# echo-dot-4th-gen.net
KiCad netlist of a schematic drawn in EasyEDA
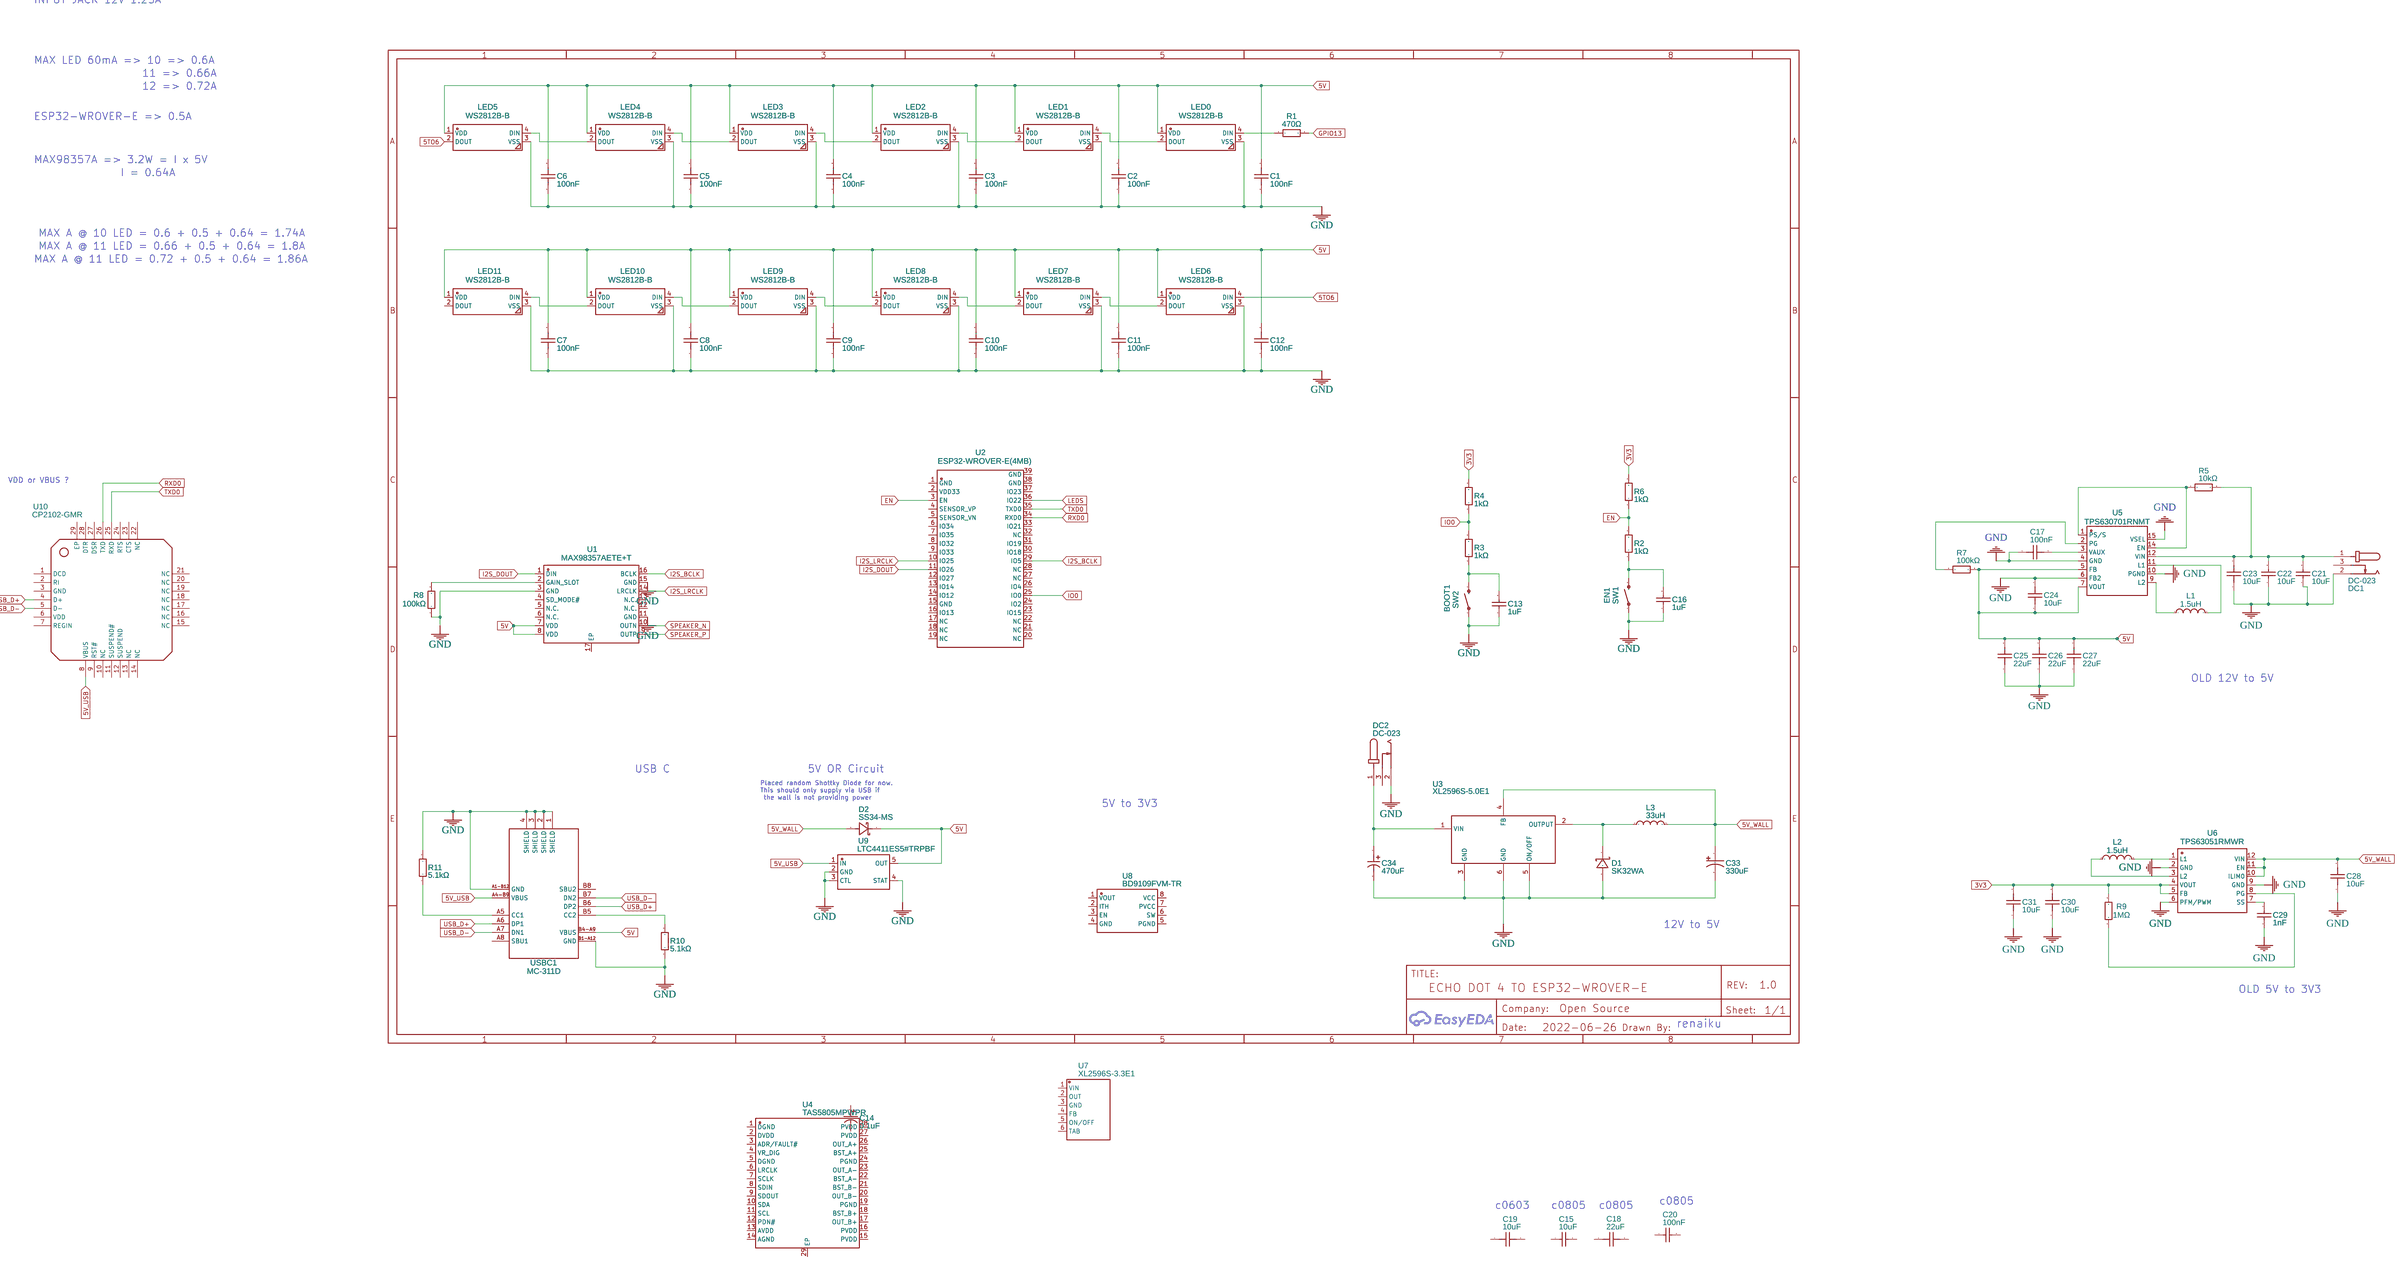
[diagram p0: schematic sheet]

(export (version "E")
  (design (tool "Eeschema 10.0.6"))
  (components
    (comp (ref "BOOT1")
      (value "SW2")
      (fields (field (name "BOM_Manufacturer Part") "?"))
      (libsource (lib "") (part "Unknown_1250_-170"))
    )
    (comp (ref "C1")
      (value "100nF")
      (fields
        (field (name "BOM_Manufacturer Part") "CC0603JRX7R7BB104")
        (field (name "BOM_Supplier Part") "C109474")
      )
      (libsource (lib "") (part "CC0603JRX7R7BB104"))
    )
    (comp (ref "C2")
      (value "100nF")
      (fields
        (field (name "BOM_Manufacturer Part") "CC0603JRX7R7BB104")
        (field (name "BOM_Supplier Part") "C109474")
      )
      (libsource (lib "") (part "CC0603JRX7R7BB104"))
    )
    (comp (ref "C3")
      (value "100nF")
      (fields
        (field (name "BOM_Manufacturer Part") "CC0603JRX7R7BB104")
        (field (name "BOM_Supplier Part") "C109474")
      )
      (libsource (lib "") (part "CC0603JRX7R7BB104"))
    )
    (comp (ref "C4")
      (value "100nF")
      (fields
        (field (name "BOM_Manufacturer Part") "CC0603JRX7R7BB104")
        (field (name "BOM_Supplier Part") "C109474")
      )
      (libsource (lib "") (part "CC0603JRX7R7BB104"))
    )
    (comp (ref "C5")
      (value "100nF")
      (fields
        (field (name "BOM_Manufacturer Part") "CC0603JRX7R7BB104")
        (field (name "BOM_Supplier Part") "C109474")
      )
      (libsource (lib "") (part "CC0603JRX7R7BB104"))
    )
    (comp (ref "C6")
      (value "100nF")
      (fields
        (field (name "BOM_Manufacturer Part") "CC0603JRX7R7BB104")
        (field (name "BOM_Supplier Part") "C109474")
      )
      (libsource (lib "") (part "CC0603JRX7R7BB104"))
    )
    (comp (ref "C7")
      (value "100nF")
      (fields
        (field (name "BOM_Manufacturer Part") "CC0603JRX7R7BB104")
        (field (name "BOM_Supplier Part") "C109474")
      )
      (libsource (lib "") (part "CC0603JRX7R7BB104"))
    )
    (comp (ref "C8")
      (value "100nF")
      (fields
        (field (name "BOM_Manufacturer Part") "CC0603JRX7R7BB104")
        (field (name "BOM_Supplier Part") "C109474")
      )
      (libsource (lib "") (part "CC0603JRX7R7BB104"))
    )
    (comp (ref "C9")
      (value "100nF")
      (fields
        (field (name "BOM_Manufacturer Part") "CC0603JRX7R7BB104")
        (field (name "BOM_Supplier Part") "C109474")
      )
      (libsource (lib "") (part "CC0603JRX7R7BB104"))
    )
    (comp (ref "C10")
      (value "100nF")
      (fields
        (field (name "BOM_Manufacturer Part") "CC0603JRX7R7BB104")
        (field (name "BOM_Supplier Part") "C109474")
      )
      (libsource (lib "") (part "CC0603JRX7R7BB104"))
    )
    (comp (ref "C11")
      (value "100nF")
      (fields
        (field (name "BOM_Manufacturer Part") "CC0603JRX7R7BB104")
        (field (name "BOM_Supplier Part") "C109474")
      )
      (libsource (lib "") (part "CC0603JRX7R7BB104"))
    )
    (comp (ref "C12")
      (value "100nF")
      (fields
        (field (name "BOM_Manufacturer Part") "CC0603JRX7R7BB104")
        (field (name "BOM_Supplier Part") "C109474")
      )
      (libsource (lib "") (part "CC0603JRX7R7BB104"))
    )
    (comp (ref "C13")
      (value "1uF")
      (fields
        (field (name "BOM_Manufacturer Part") "CC0603KRX5R6BB105")
        (field (name "BOM_Supplier Part") "C106214")
      )
      (libsource (lib "") (part "CC0603KRX5R6BB105"))
    )
    (comp (ref "C14")
      (value "0.1uF")
      (fields
        (field (name "BOM_Manufacturer Part") "0.1uF 50V 4*7")
        (field (name "BOM_Supplier Part") "C45664")
      )
      (libsource (lib "") (part "0.1uF 50V 4*7"))
    )
    (comp (ref "C15")
      (value "10uF")
      (fields
        (field (name "BOM_Manufacturer Part") "CL21A106KAYNNNE")
        (field (name "BOM_Supplier Part") "C15850")
      )
      (libsource (lib "") (part "CL21A106KAYNNNE_1"))
    )
    (comp (ref "C16")
      (value "1uF")
      (fields
        (field (name "BOM_Manufacturer Part") "CC0603KRX5R6BB105")
        (field (name "BOM_Supplier Part") "C106214")
      )
      (libsource (lib "") (part "CC0603KRX5R6BB105"))
    )
    (comp (ref "C17")
      (value "100nF")
      (fields
        (field (name "BOM_Manufacturer Part") "CC0603KRX7R9BB104")
        (field (name "BOM_Supplier Part") "C14663")
      )
      (libsource (lib "") (part "CC0603KRX7R9BB104"))
    )
    (comp (ref "C18")
      (value "22uF")
      (fields
        (field (name "BOM_Manufacturer Part") "CL21A226MAQNNNE")
        (field (name "BOM_Supplier Part") "C45783")
      )
      (libsource (lib "") (part "CL21A226MAQNNNE"))
    )
    (comp (ref "C19")
      (value "10uF")
      (fields
        (field (name "BOM_Manufacturer Part") "CL10A106MA8NRNC")
        (field (name "BOM_Supplier Part") "C96446")
      )
      (libsource (lib "") (part "CL10A106MA8NRNC_2"))
    )
    (comp (ref "C20")
      (value "100nF")
      (fields
        (field (name "BOM_Manufacturer Part") "CC0805KRX7R9BB104")
        (field (name "BOM_Supplier Part") "C49678")
      )
      (libsource (lib "") (part "CC0805KRX7R9BB104"))
    )
    (comp (ref "C21")
      (value "10uF")
      (fields
        (field (name "BOM_Manufacturer Part") "CL21A106KAYNNNE")
        (field (name "BOM_Supplier Part") "C15850")
      )
      (libsource (lib "") (part "CL21A106KAYNNNE"))
    )
    (comp (ref "C22")
      (value "10uF")
      (fields
        (field (name "BOM_Manufacturer Part") "CL21A106KAYNNNE")
        (field (name "BOM_Supplier Part") "C15850")
      )
      (libsource (lib "") (part "CL21A106KAYNNNE"))
    )
    (comp (ref "C23")
      (value "10uF")
      (fields
        (field (name "BOM_Manufacturer Part") "CL10A106MA8NRNC")
        (field (name "BOM_Supplier Part") "C96446")
      )
      (libsource (lib "") (part "CL10A106MA8NRNC"))
    )
    (comp (ref "C24")
      (value "10uF")
      (fields
        (field (name "BOM_Manufacturer Part") "CL10A106MA8NRNC")
        (field (name "BOM_Supplier Part") "C96446")
      )
      (libsource (lib "") (part "CL10A106MA8NRNC_1"))
    )
    (comp (ref "C25")
      (value "22uF")
      (fields
        (field (name "BOM_Manufacturer Part") "CL21A226MAQNNNE")
        (field (name "BOM_Supplier Part") "C45783")
      )
      (libsource (lib "") (part "CL21A226MAQNNNE_1"))
    )
    (comp (ref "C26")
      (value "22uF")
      (fields
        (field (name "BOM_Manufacturer Part") "CL21A226MAQNNNE")
        (field (name "BOM_Supplier Part") "C45783")
      )
      (libsource (lib "") (part "CL21A226MAQNNNE_1"))
    )
    (comp (ref "C27")
      (value "22uF")
      (fields
        (field (name "BOM_Manufacturer Part") "CL21A226MAQNNNE")
        (field (name "BOM_Supplier Part") "C45783")
      )
      (libsource (lib "") (part "CL21A226MAQNNNE_1"))
    )
    (comp (ref "C28")
      (value "10uF")
      (fields
        (field (name "BOM_Manufacturer Part") "CL10A106MA8NRNC")
        (field (name "BOM_Supplier Part") "C96446")
      )
      (libsource (lib "") (part "CL10A106MA8NRNC"))
    )
    (comp (ref "C29")
      (value "1nF")
      (fields
        (field (name "BOM_Manufacturer Part") "CL10B102KB8NNNC")
        (field (name "BOM_Supplier Part") "C1588")
      )
      (libsource (lib "") (part "CL10B102KB8NNNC"))
    )
    (comp (ref "C30")
      (value "10uF")
      (fields
        (field (name "BOM_Manufacturer Part") "CL10A106MA8NRNC")
        (field (name "BOM_Supplier Part") "C96446")
      )
      (libsource (lib "") (part "CL10A106MA8NRNC"))
    )
    (comp (ref "C31")
      (value "10uF")
      (fields
        (field (name "BOM_Manufacturer Part") "CL10A106MA8NRNC")
        (field (name "BOM_Supplier Part") "C96446")
      )
      (libsource (lib "") (part "CL10A106MA8NRNC"))
    )
    (comp (ref "C33")
      (value "330uF")
      (fields
        (field (name "BOM_Manufacturer Part") "RVT1C331M0810")
        (field (name "BOM_Supplier Part") "C87872")
      )
      (libsource (lib "") (part "RVT1C331M0810"))
    )
    (comp (ref "C34")
      (value "470uF")
      (fields
        (field (name "BOM_Manufacturer Part") "RVT1C471M0607")
        (field (name "BOM_Supplier Part") "C2977552")
      )
      (libsource (lib "") (part "RVT1C471M0607"))
    )
    (comp (ref "D1")
      (value "SK32WA")
      (fields (field (name "BOM_Supplier Part") "C183472"))
      (libsource (lib "") (part "SK32WA"))
    )
    (comp (ref "D2")
      (value "SS34-MS")
      (fields (field (name "BOM_Supplier Part") "C2836396"))
      (libsource (lib "") (part "SS34-MS"))
    )
    (comp (ref "DC1")
      (value "DC-023")
      (fields (field (name "BOM_Supplier Part") "C2689666"))
      (libsource (lib "") (part "DC-023"))
    )
    (comp (ref "DC2")
      (value "DC-023")
      (fields (field (name "BOM_Supplier Part") "C2689666"))
      (libsource (lib "") (part "DC-023_1"))
    )
    (comp (ref "EN1")
      (value "SW1")
      (fields (field (name "BOM_Manufacturer Part") "?"))
      (libsource (lib "") (part "Unknown_1435_-175"))
    )
    (comp (ref "L1")
      (value "1.5uH")
      (fields
        (field (name "BOM_Manufacturer Part") "MLF1608A1R5JT000")
        (field (name "BOM_Supplier Part") "C87514")
      )
      (libsource (lib "") (part "MLF1608A1R5JT000"))
    )
    (comp (ref "L2")
      (value "1.5uH")
      (fields
        (field (name "BOM_Manufacturer Part") "MLF1608A1R5JT000")
        (field (name "BOM_Supplier Part") "C87514")
      )
      (libsource (lib "") (part "MLF1608A1R5JT000_1"))
    )
    (comp (ref "L3")
      (value "33uH")
      (fields
        (field (name "BOM_Manufacturer Part") "CYH127-33UH")
        (field (name "BOM_Supplier Part") "C2929502")
      )
      (libsource (lib "") (part "CYH127-33UH"))
    )
    (comp (ref "LED0")
      (value "WS2812B-B")
      (fields (field (name "BOM_Supplier Part") "C114586"))
      (libsource (lib "") (part "WS2812B-B"))
    )
    (comp (ref "LED1")
      (value "WS2812B-B")
      (fields (field (name "BOM_Supplier Part") "C114586"))
      (libsource (lib "") (part "WS2812B-B"))
    )
    (comp (ref "LED2")
      (value "WS2812B-B")
      (fields (field (name "BOM_Supplier Part") "C114586"))
      (libsource (lib "") (part "WS2812B-B"))
    )
    (comp (ref "LED3")
      (value "WS2812B-B")
      (fields (field (name "BOM_Supplier Part") "C114586"))
      (libsource (lib "") (part "WS2812B-B"))
    )
    (comp (ref "LED4")
      (value "WS2812B-B")
      (fields (field (name "BOM_Supplier Part") "C114586"))
      (libsource (lib "") (part "WS2812B-B"))
    )
    (comp (ref "LED5")
      (value "WS2812B-B")
      (fields (field (name "BOM_Supplier Part") "C114586"))
      (libsource (lib "") (part "WS2812B-B"))
    )
    (comp (ref "LED6")
      (value "WS2812B-B")
      (fields (field (name "BOM_Supplier Part") "C114586"))
      (libsource (lib "") (part "WS2812B-B"))
    )
    (comp (ref "LED7")
      (value "WS2812B-B")
      (fields (field (name "BOM_Supplier Part") "C114586"))
      (libsource (lib "") (part "WS2812B-B"))
    )
    (comp (ref "LED8")
      (value "WS2812B-B")
      (fields (field (name "BOM_Supplier Part") "C114586"))
      (libsource (lib "") (part "WS2812B-B"))
    )
    (comp (ref "LED9")
      (value "WS2812B-B")
      (fields (field (name "BOM_Supplier Part") "C114586"))
      (libsource (lib "") (part "WS2812B-B"))
    )
    (comp (ref "LED10")
      (value "WS2812B-B")
      (fields (field (name "BOM_Supplier Part") "C114586"))
      (libsource (lib "") (part "WS2812B-B"))
    )
    (comp (ref "LED11")
      (value "WS2812B-B")
      (fields (field (name "BOM_Supplier Part") "C114586"))
      (libsource (lib "") (part "WS2812B-B"))
    )
    (comp (ref "R1")
      (value "470Ω")
      (fields
        (field (name "BOM_Manufacturer Part") "CR0603FA4700G")
        (field (name "BOM_Supplier Part") "C101061")
      )
      (libsource (lib "") (part "CR0603FA4700G"))
    )
    (comp (ref "R2")
      (value "1kΩ")
      (fields
        (field (name "BOM_Manufacturer Part") "CR0603FA1001G")
        (field (name "BOM_Supplier Part") "C126900")
      )
      (libsource (lib "") (part "CR0603FA1001G_C126900"))
    )
    (comp (ref "R3")
      (value "1kΩ")
      (fields
        (field (name "BOM_Manufacturer Part") "CR0603FA1001G")
        (field (name "BOM_Supplier Part") "C126900")
      )
      (libsource (lib "") (part "CR0603FA1001G_C126900"))
    )
    (comp (ref "R4")
      (value "1kΩ")
      (fields
        (field (name "BOM_Manufacturer Part") "CR0603FA1001G")
        (field (name "BOM_Supplier Part") "C126900")
      )
      (libsource (lib "") (part "CR0603FA1001G_C126900"))
    )
    (comp (ref "R5")
      (value "10kΩ")
      (fields
        (field (name "BOM_Manufacturer Part") "0603WAF1002T5E")
        (field (name "BOM_Supplier Part") "C25804")
      )
      (libsource (lib "") (part "0603WAF1002T5E"))
    )
    (comp (ref "R6")
      (value "1kΩ")
      (fields
        (field (name "BOM_Manufacturer Part") "CR0603FA1001G")
        (field (name "BOM_Supplier Part") "C126900")
      )
      (libsource (lib "") (part "CR0603FA1001G_C126900"))
    )
    (comp (ref "R7")
      (value "100kΩ")
      (fields
        (field (name "BOM_Manufacturer Part") "0603WAF1003T5E")
        (field (name "BOM_Supplier Part") "C25803")
      )
      (libsource (lib "") (part "0603WAF1003T5E"))
    )
    (comp (ref "R8")
      (value "100kΩ")
      (fields
        (field (name "BOM_Manufacturer Part") "0603WAF1003T5E")
        (field (name "BOM_Supplier Part") "C25803")
      )
      (libsource (lib "") (part "0603WAF1003T5E_1"))
    )
    (comp (ref "R9")
      (value "1MΩ")
      (fields
        (field (name "BOM_Manufacturer Part") "0603WAF1004T5E")
        (field (name "BOM_Supplier Part") "C22935")
      )
      (libsource (lib "") (part "0603WAF1004T5E"))
    )
    (comp (ref "R10")
      (value "5.1kΩ")
      (fields
        (field (name "BOM_Manufacturer Part") "0603WAF5101T5E")
        (field (name "BOM_Supplier Part") "C23186")
      )
      (libsource (lib "") (part "0603WAF5101T5E"))
    )
    (comp (ref "R11")
      (value "5.1kΩ")
      (fields
        (field (name "BOM_Manufacturer Part") "0603WAF5101T5E")
        (field (name "BOM_Supplier Part") "C23186")
      )
      (libsource (lib "") (part "0603WAF5101T5E"))
    )
    (comp (ref "U1")
      (value "MAX98357AETE+T")
      (fields (field (name "BOM_Supplier Part") "C910544"))
      (libsource (lib "") (part "MAX98357AETE+T"))
    )
    (comp (ref "U2")
      (value "ESP32-WROVER-E(4MB)")
      (fields (field (name "BOM_Supplier Part") "C529587"))
      (libsource (lib "") (part "ESP32-WROVER-E(4MB)"))
    )
    (comp (ref "U3")
      (value "XL2596S-5.0E1")
      (fields (field (name "BOM_Supplier Part") "C74190"))
      (libsource (lib "") (part "XL2596S-5.0E1"))
    )
    (comp (ref "U4")
      (value "TAS5805MPWPR")
      (fields (field (name "BOM_Supplier Part") "C478472"))
      (libsource (lib "") (part "TAS5805MPWPR"))
    )
    (comp (ref "U5")
      (value "TPS630701RNMT")
      (fields (field (name "BOM_Supplier Part") "C181473"))
      (libsource (lib "") (part "TPS630701RNMT"))
    )
    (comp (ref "U6")
      (value "TPS63051RMWR")
      (fields (field (name "BOM_Supplier Part") "C139412"))
      (libsource (lib "") (part "TPS63051RMWR"))
    )
    (comp (ref "U7")
      (value "XL2596S-3.3E1")
      (fields (field (name "BOM_Supplier Part") "C74189"))
      (libsource (lib "") (part "XL2596S-3.3E1"))
    )
    (comp (ref "U8")
      (value "BD9109FVM-TR")
      (fields (field (name "BOM_Supplier Part") "C308604"))
      (libsource (lib "") (part "BD9109FVM-TR"))
    )
    (comp (ref "U9")
      (value "LTC4411ES5#TRPBF")
      (fields (field (name "BOM_Supplier Part") "C459901"))
      (libsource (lib "") (part "LTC4411ES5#TRPBF"))
    )
    (comp (ref "U10")
      (value "CP2102-GMR")
      (fields (field (name "BOM_Supplier Part") "C6568"))
      (libsource (lib "") (part "CP2102-GMR"))
    )
    (comp (ref "USBC1")
      (value "MC-311D")
      (fields (field (name "BOM_Supplier Part") "C136423"))
      (libsource (lib "") (part "MC-311D"))
    )
  )
  (nets
    (net (code "1") (name "3V3") (class "Default")
      (node (ref "C30") (pin "2") (pinfunction "2_2") (pintype "unspecified"))
      (node (ref "C31") (pin "2") (pinfunction "2_2") (pintype "unspecified"))
      (node (ref "R4") (pin "2") (pinfunction "2_2") (pintype "input"))
      (node (ref "R6") (pin "2") (pinfunction "2_2") (pintype "input"))
      (node (ref "R9") (pin "2") (pinfunction "2_2") (pintype "input"))
      (node (ref "U6") (pin "4") (pinfunction "VOUT_4") (pintype "unspecified"))
      (node (ref "U6") (pin "5") (pinfunction "FB_5") (pintype "unspecified"))
    )
    (net (code "2") (name "5TO6") (class "Default")
      (node (ref "LED5") (pin "2") (pinfunction "DOUT_2") (pintype "unspecified"))
      (node (ref "LED6") (pin "4") (pinfunction "DIN_4") (pintype "unspecified"))
    )
    (net (code "3") (name "5V") (class "Default")
      (node (ref "C1") (pin "2") (pinfunction "2_2") (pintype "unspecified"))
      (node (ref "C10") (pin "2") (pinfunction "2_2") (pintype "unspecified"))
      (node (ref "C11") (pin "2") (pinfunction "2_2") (pintype "unspecified"))
      (node (ref "C12") (pin "2") (pinfunction "2_2") (pintype "unspecified"))
      (node (ref "C2") (pin "2") (pinfunction "2_2") (pintype "unspecified"))
      (node (ref "C24") (pin "2") (pinfunction "2_2") (pintype "unspecified"))
      (node (ref "C25") (pin "2") (pinfunction "2_2") (pintype "unspecified"))
      (node (ref "C26") (pin "2") (pinfunction "2_2") (pintype "unspecified"))
      (node (ref "C27") (pin "2") (pinfunction "2_2") (pintype "unspecified"))
      (node (ref "C3") (pin "2") (pinfunction "2_2") (pintype "unspecified"))
      (node (ref "C4") (pin "2") (pinfunction "2_2") (pintype "unspecified"))
      (node (ref "C5") (pin "2") (pinfunction "2_2") (pintype "unspecified"))
      (node (ref "C6") (pin "2") (pinfunction "2_2") (pintype "unspecified"))
      (node (ref "C7") (pin "2") (pinfunction "2_2") (pintype "unspecified"))
      (node (ref "C8") (pin "2") (pinfunction "2_2") (pintype "unspecified"))
      (node (ref "C9") (pin "2") (pinfunction "2_2") (pintype "unspecified"))
      (node (ref "D2") (pin "1") (pinfunction "A_1") (pintype "unspecified"))
      (node (ref "LED0") (pin "1") (pinfunction "VDD_1") (pintype "unspecified"))
      (node (ref "LED1") (pin "1") (pinfunction "VDD_1") (pintype "unspecified"))
      (node (ref "LED10") (pin "1") (pinfunction "VDD_1") (pintype "unspecified"))
      (node (ref "LED11") (pin "1") (pinfunction "VDD_1") (pintype "unspecified"))
      (node (ref "LED2") (pin "1") (pinfunction "VDD_1") (pintype "unspecified"))
      (node (ref "LED3") (pin "1") (pinfunction "VDD_1") (pintype "unspecified"))
      (node (ref "LED4") (pin "1") (pinfunction "VDD_1") (pintype "unspecified"))
      (node (ref "LED5") (pin "1") (pinfunction "VDD_1") (pintype "unspecified"))
      (node (ref "LED6") (pin "1") (pinfunction "VDD_1") (pintype "unspecified"))
      (node (ref "LED7") (pin "1") (pinfunction "VDD_1") (pintype "unspecified"))
      (node (ref "LED8") (pin "1") (pinfunction "VDD_1") (pintype "unspecified"))
      (node (ref "LED9") (pin "1") (pinfunction "VDD_1") (pintype "unspecified"))
      (node (ref "R7") (pin "2") (pinfunction "2_2") (pintype "input"))
      (node (ref "U1") (pin "7") (pinfunction "VDD_7") (pintype "unspecified"))
      (node (ref "U1") (pin "8") (pinfunction "VDD_8") (pintype "unspecified"))
      (node (ref "U5") (pin "5") (pinfunction "FB_5") (pintype "unspecified"))
      (node (ref "U5") (pin "7") (pinfunction "VOUT_7") (pintype "unspecified"))
      (node (ref "U9") (pin "5") (pinfunction "OUT_5") (pintype "unspecified"))
      (node (ref "USBC1") (pin "B4-A9") (pinfunction "VBUS_B4-A9") (pintype "unspecified"))
    )
    (net (code "4") (name "5V_USB") (class "Default")
      (node (ref "U10") (pin "8") (pinfunction "VBUS_8") (pintype "unspecified"))
      (node (ref "U9") (pin "1") (pinfunction "IN_1") (pintype "unspecified"))
      (node (ref "USBC1") (pin "A4-B9") (pinfunction "VBUS_A4-B9") (pintype "unspecified"))
    )
    (net (code "5") (name "5V_WALL") (class "Default")
      (node (ref "C28") (pin "2") (pinfunction "2_2") (pintype "unspecified"))
      (node (ref "C33") (pin "1") (pinfunction "1_1") (pintype "unspecified"))
      (node (ref "D2") (pin "2") (pinfunction "K_2") (pintype "unspecified"))
      (node (ref "L3") (pin "2") (pinfunction "2_2") (pintype "unspecified"))
      (node (ref "U3") (pin "4") (pinfunction "FB_4") (pintype "unspecified"))
      (node (ref "U6") (pin "10") (pinfunction "ILIM0_10") (pintype "unspecified"))
      (node (ref "U6") (pin "11") (pinfunction "EN_11") (pintype "unspecified"))
      (node (ref "U6") (pin "12") (pinfunction "VIN_12") (pintype "unspecified"))
    )
    (net (code "6") (name "EN") (class "Default")
      (node (ref "R2") (pin "2") (pinfunction "2_2") (pintype "input"))
      (node (ref "R6") (pin "1") (pinfunction "1_1") (pintype "input"))
      (node (ref "U2") (pin "3") (pinfunction "EN_3") (pintype "unspecified"))
    )
    (net (code "7") (name "GND") (class "Default")
      (node (ref "BOOT1") (pin "1") (pinfunction "1_1") (pintype "unspecified"))
      (node (ref "C1") (pin "1") (pinfunction "1_1") (pintype "unspecified"))
      (node (ref "C10") (pin "1") (pinfunction "1_1") (pintype "unspecified"))
      (node (ref "C11") (pin "1") (pinfunction "1_1") (pintype "unspecified"))
      (node (ref "C12") (pin "1") (pinfunction "1_1") (pintype "unspecified"))
      (node (ref "C13") (pin "1") (pinfunction "1_1") (pintype "input"))
      (node (ref "C16") (pin "1") (pinfunction "1_1") (pintype "input"))
      (node (ref "C17") (pin "1") (pinfunction "1_1") (pintype "unspecified"))
      (node (ref "C2") (pin "1") (pinfunction "1_1") (pintype "unspecified"))
      (node (ref "C21") (pin "1") (pinfunction "1_1") (pintype "input"))
      (node (ref "C22") (pin "1") (pinfunction "1_1") (pintype "input"))
      (node (ref "C23") (pin "1") (pinfunction "1_1") (pintype "unspecified"))
      (node (ref "C24") (pin "1") (pinfunction "1_1") (pintype "unspecified"))
      (node (ref "C25") (pin "1") (pinfunction "1_1") (pintype "unspecified"))
      (node (ref "C26") (pin "1") (pinfunction "1_1") (pintype "unspecified"))
      (node (ref "C27") (pin "1") (pinfunction "1_1") (pintype "unspecified"))
      (node (ref "C28") (pin "1") (pinfunction "1_1") (pintype "unspecified"))
      (node (ref "C29") (pin "1") (pinfunction "1_1") (pintype "input"))
      (node (ref "C3") (pin "1") (pinfunction "1_1") (pintype "unspecified"))
      (node (ref "C30") (pin "1") (pinfunction "1_1") (pintype "unspecified"))
      (node (ref "C31") (pin "1") (pinfunction "1_1") (pintype "unspecified"))
      (node (ref "C33") (pin "2") (pinfunction "2_2") (pintype "unspecified"))
      (node (ref "C34") (pin "2") (pinfunction "2_2") (pintype "input"))
      (node (ref "C4") (pin "1") (pinfunction "1_1") (pintype "unspecified"))
      (node (ref "C5") (pin "1") (pinfunction "1_1") (pintype "unspecified"))
      (node (ref "C6") (pin "1") (pinfunction "1_1") (pintype "unspecified"))
      (node (ref "C7") (pin "1") (pinfunction "1_1") (pintype "unspecified"))
      (node (ref "C8") (pin "1") (pinfunction "1_1") (pintype "unspecified"))
      (node (ref "C9") (pin "1") (pinfunction "1_1") (pintype "unspecified"))
      (node (ref "D1") (pin "2") (pinfunction "2_2") (pintype "unspecified"))
      (node (ref "DC1") (pin "2") (pinfunction "2_2") (pintype "unspecified"))
      (node (ref "DC2") (pin "2") (pinfunction "2_2") (pintype "unspecified"))
      (node (ref "EN1") (pin "1") (pinfunction "1_1") (pintype "unspecified"))
      (node (ref "LED0") (pin "3") (pinfunction "VSS_3") (pintype "unspecified"))
      (node (ref "LED1") (pin "3") (pinfunction "VSS_3") (pintype "unspecified"))
      (node (ref "LED10") (pin "3") (pinfunction "VSS_3") (pintype "unspecified"))
      (node (ref "LED11") (pin "3") (pinfunction "VSS_3") (pintype "unspecified"))
      (node (ref "LED2") (pin "3") (pinfunction "VSS_3") (pintype "unspecified"))
      (node (ref "LED3") (pin "3") (pinfunction "VSS_3") (pintype "unspecified"))
      (node (ref "LED4") (pin "3") (pinfunction "VSS_3") (pintype "unspecified"))
      (node (ref "LED5") (pin "3") (pinfunction "VSS_3") (pintype "unspecified"))
      (node (ref "LED6") (pin "3") (pinfunction "VSS_3") (pintype "unspecified"))
      (node (ref "LED7") (pin "3") (pinfunction "VSS_3") (pintype "unspecified"))
      (node (ref "LED8") (pin "3") (pinfunction "VSS_3") (pintype "unspecified"))
      (node (ref "LED9") (pin "3") (pinfunction "VSS_3") (pintype "unspecified"))
      (node (ref "R10") (pin "1") (pinfunction "1_1") (pintype "input"))
      (node (ref "R11") (pin "2") (pinfunction "2_2") (pintype "input"))
      (node (ref "R8") (pin "1") (pinfunction "1_1") (pintype "input"))
      (node (ref "U1") (pin "11") (pinfunction "GND_11") (pintype "unspecified"))
      (node (ref "U1") (pin "15") (pinfunction "GND_15") (pintype "unspecified"))
      (node (ref "U1") (pin "3") (pinfunction "GND_3") (pintype "unspecified"))
      (node (ref "U3") (pin "3") (pinfunction "GND_3") (pintype "unspecified"))
      (node (ref "U3") (pin "5") (pinfunction "ON/OFF_5") (pintype "unspecified"))
      (node (ref "U3") (pin "6") (pinfunction "GND_6") (pintype "unspecified"))
      (node (ref "U5") (pin "10") (pinfunction "PGND_10") (pintype "unspecified"))
      (node (ref "U5") (pin "15") (pinfunction "VSEL_15") (pintype "unspecified"))
      (node (ref "U5") (pin "4") (pinfunction "GND_4") (pintype "unspecified"))
      (node (ref "U5") (pin "6") (pinfunction "FB2_6") (pintype "unspecified"))
      (node (ref "U6") (pin "2") (pinfunction "GND_2") (pintype "unspecified"))
      (node (ref "U6") (pin "6") (pinfunction "PFM/PWM_6") (pintype "unspecified"))
      (node (ref "U6") (pin "9") (pinfunction "GND_9") (pintype "unspecified"))
      (node (ref "U9") (pin "2") (pinfunction "GND_2") (pintype "unspecified"))
      (node (ref "U9") (pin "3") (pinfunction "CTL_3") (pintype "unspecified"))
      (node (ref "U9") (pin "4") (pinfunction "STAT_4") (pintype "unspecified"))
      (node (ref "USBC1") (pin "1") (pinfunction "SHIELD_1") (pintype "unspecified"))
      (node (ref "USBC1") (pin "2") (pinfunction "SHIELD_2") (pintype "unspecified"))
      (node (ref "USBC1") (pin "3") (pinfunction "SHIELD_3") (pintype "unspecified"))
      (node (ref "USBC1") (pin "4") (pinfunction "SHIELD_4") (pintype "unspecified"))
      (node (ref "USBC1") (pin "A1-B12") (pinfunction "GND_A1-B12") (pintype "unspecified"))
      (node (ref "USBC1") (pin "B1-A12") (pinfunction "GND_B1-A12") (pintype "unspecified"))
    )
    (net (code "8") (name "GPIO13") (class "Default")
      (node (ref "R1") (pin "2") (pinfunction "2_2") (pintype "input"))
    )
    (net (code "9") (name "I2S_BCLK") (class "Default")
      (node (ref "U1") (pin "16") (pinfunction "BCLK_16") (pintype "unspecified"))
      (node (ref "U2") (pin "29") (pinfunction "IO5_29") (pintype "unspecified"))
    )
    (net (code "10") (name "I2S_DOUT") (class "Default")
      (node (ref "U1") (pin "1") (pinfunction "DIN_1") (pintype "unspecified"))
      (node (ref "U2") (pin "11") (pinfunction "IO26_11") (pintype "unspecified"))
    )
    (net (code "11") (name "I2S_LRCLK") (class "Default")
      (node (ref "U1") (pin "14") (pinfunction "LRCLK_14") (pintype "unspecified"))
      (node (ref "U2") (pin "10") (pinfunction "IO25_10") (pintype "unspecified"))
    )
    (net (code "12") (name "IO0") (class "Default")
      (node (ref "R3") (pin "2") (pinfunction "2_2") (pintype "input"))
      (node (ref "R4") (pin "1") (pinfunction "1_1") (pintype "input"))
      (node (ref "U2") (pin "25") (pinfunction "IO0_25") (pintype "unspecified"))
    )
    (net (code "13") (name "LEDS") (class "Default")
      (node (ref "U2") (pin "36") (pinfunction "IO22_36") (pintype "unspecified"))
    )
    (net (code "14") (name "Net-(BOOT1-Pad2)") (class "Default")
      (node (ref "BOOT1") (pin "2") (pinfunction "2_2") (pintype "unspecified"))
      (node (ref "C13") (pin "2") (pinfunction "2_2") (pintype "input"))
      (node (ref "R3") (pin "1") (pinfunction "1_1") (pintype "input"))
    )
    (net (code "15") (name "Net-(C16-Pad2)") (class "Default")
      (node (ref "C16") (pin "2") (pinfunction "2_2") (pintype "input"))
      (node (ref "EN1") (pin "2") (pinfunction "2_2") (pintype "unspecified"))
      (node (ref "R2") (pin "1") (pinfunction "1_1") (pintype "input"))
    )
    (net (code "16") (name "Net-(LED0-DIN)") (class "Default")
      (node (ref "LED0") (pin "4") (pinfunction "DIN_4") (pintype "unspecified"))
      (node (ref "R1") (pin "1") (pinfunction "1_1") (pintype "input"))
    )
    (net (code "17") (name "Net-(LED0-DOUT)") (class "Default")
      (node (ref "LED0") (pin "2") (pinfunction "DOUT_2") (pintype "unspecified"))
      (node (ref "LED1") (pin "4") (pinfunction "DIN_4") (pintype "unspecified"))
    )
    (net (code "18") (name "Net-(LED1-DOUT)") (class "Default")
      (node (ref "LED1") (pin "2") (pinfunction "DOUT_2") (pintype "unspecified"))
      (node (ref "LED2") (pin "4") (pinfunction "DIN_4") (pintype "unspecified"))
    )
    (net (code "19") (name "Net-(LED2-DOUT)") (class "Default")
      (node (ref "LED2") (pin "2") (pinfunction "DOUT_2") (pintype "unspecified"))
      (node (ref "LED3") (pin "4") (pinfunction "DIN_4") (pintype "unspecified"))
    )
    (net (code "20") (name "Net-(LED3-DOUT)") (class "Default")
      (node (ref "LED3") (pin "2") (pinfunction "DOUT_2") (pintype "unspecified"))
      (node (ref "LED4") (pin "4") (pinfunction "DIN_4") (pintype "unspecified"))
    )
    (net (code "21") (name "Net-(LED4-DOUT)") (class "Default")
      (node (ref "LED4") (pin "2") (pinfunction "DOUT_2") (pintype "unspecified"))
      (node (ref "LED5") (pin "4") (pinfunction "DIN_4") (pintype "unspecified"))
    )
    (net (code "22") (name "Net-(LED6-DOUT)") (class "Default")
      (node (ref "LED6") (pin "2") (pinfunction "DOUT_2") (pintype "unspecified"))
      (node (ref "LED7") (pin "4") (pinfunction "DIN_4") (pintype "unspecified"))
    )
    (net (code "23") (name "Net-(LED7-DOUT)") (class "Default")
      (node (ref "LED7") (pin "2") (pinfunction "DOUT_2") (pintype "unspecified"))
      (node (ref "LED8") (pin "4") (pinfunction "DIN_4") (pintype "unspecified"))
    )
    (net (code "24") (name "Net-(LED8-DOUT)") (class "Default")
      (node (ref "LED8") (pin "2") (pinfunction "DOUT_2") (pintype "unspecified"))
      (node (ref "LED9") (pin "4") (pinfunction "DIN_4") (pintype "unspecified"))
    )
    (net (code "25") (name "Net-(LED10-DIN)") (class "Default")
      (node (ref "LED10") (pin "4") (pinfunction "DIN_4") (pintype "unspecified"))
      (node (ref "LED9") (pin "2") (pinfunction "DOUT_2") (pintype "unspecified"))
    )
    (net (code "26") (name "Net-(LED10-DOUT)") (class "Default")
      (node (ref "LED10") (pin "2") (pinfunction "DOUT_2") (pintype "unspecified"))
      (node (ref "LED11") (pin "4") (pinfunction "DIN_4") (pintype "unspecified"))
    )
    (net (code "27") (name "Net-(U1-GAIN_SLOT)") (class "Default")
      (node (ref "R8") (pin "2") (pinfunction "2_2") (pintype "input"))
      (node (ref "U1") (pin "2") (pinfunction "GAIN_SLOT_2") (pintype "unspecified"))
    )
    (net (code "28") (name "Net-(U3-OUTPUT)") (class "Default")
      (node (ref "D1") (pin "1") (pinfunction "1_1") (pintype "unspecified"))
      (node (ref "L3") (pin "1") (pinfunction "1_1") (pintype "unspecified"))
      (node (ref "U3") (pin "2") (pinfunction "OUTPUT_2") (pintype "unspecified"))
    )
    (net (code "29") (name "Net-(U3-VIN)") (class "Default")
      (node (ref "C34") (pin "1") (pinfunction "1_1") (pintype "input"))
      (node (ref "DC2") (pin "1") (pinfunction "1_1") (pintype "unspecified"))
      (node (ref "U3") (pin "1") (pinfunction "VIN_1") (pintype "unspecified"))
    )
    (net (code "30") (name "Net-(U5-EN)") (class "Default")
      (node (ref "R5") (pin "1") (pinfunction "1_1") (pintype "input"))
      (node (ref "U5") (pin "1") (pinfunction "PS/S_1") (pintype "unspecified"))
      (node (ref "U5") (pin "14") (pinfunction "EN_14") (pintype "unspecified"))
    )
    (net (code "31") (name "Net-(U5-L1)") (class "Default")
      (node (ref "L1") (pin "2") (pinfunction "2_2") (pintype "unspecified"))
      (node (ref "U5") (pin "11") (pinfunction "L1_11") (pintype "unspecified"))
    )
    (net (code "32") (name "Net-(U5-L2)") (class "Default")
      (node (ref "L1") (pin "1") (pinfunction "1_1") (pintype "unspecified"))
      (node (ref "U5") (pin "9") (pinfunction "L2_9") (pintype "unspecified"))
    )
    (net (code "33") (name "Net-(U5-PG)") (class "Default")
      (node (ref "R7") (pin "1") (pinfunction "1_1") (pintype "input"))
      (node (ref "U5") (pin "2") (pinfunction "PG_2") (pintype "unspecified"))
    )
    (net (code "34") (name "Net-(U5-VAUX)") (class "Default")
      (node (ref "C17") (pin "2") (pinfunction "2_2") (pintype "unspecified"))
      (node (ref "U5") (pin "3") (pinfunction "VAUX_3") (pintype "unspecified"))
    )
    (net (code "35") (name "Net-(U5-VIN)") (class "Default")
      (node (ref "C21") (pin "2") (pinfunction "2_2") (pintype "input"))
      (node (ref "C22") (pin "2") (pinfunction "2_2") (pintype "input"))
      (node (ref "C23") (pin "2") (pinfunction "2_2") (pintype "unspecified"))
      (node (ref "DC1") (pin "1") (pinfunction "1_1") (pintype "unspecified"))
      (node (ref "R5") (pin "2") (pinfunction "2_2") (pintype "input"))
      (node (ref "U5") (pin "12") (pinfunction "VIN_12") (pintype "unspecified"))
    )
    (net (code "36") (name "Net-(U6-L1)") (class "Default")
      (node (ref "L2") (pin "2") (pinfunction "2_2") (pintype "unspecified"))
      (node (ref "U6") (pin "1") (pinfunction "L1_1") (pintype "unspecified"))
    )
    (net (code "37") (name "Net-(U6-L2)") (class "Default")
      (node (ref "L2") (pin "1") (pinfunction "1_1") (pintype "unspecified"))
      (node (ref "U6") (pin "3") (pinfunction "L2_3") (pintype "unspecified"))
    )
    (net (code "38") (name "Net-(U6-PG)") (class "Default")
      (node (ref "R9") (pin "1") (pinfunction "1_1") (pintype "input"))
      (node (ref "U6") (pin "8") (pinfunction "PG_8") (pintype "unspecified"))
    )
    (net (code "39") (name "Net-(U6-SS)") (class "Default")
      (node (ref "C29") (pin "2") (pinfunction "2_2") (pintype "input"))
      (node (ref "U6") (pin "7") (pinfunction "SS_7") (pintype "unspecified"))
    )
    (net (code "40") (name "Net-(USBC1-CC1)") (class "Default")
      (node (ref "R11") (pin "1") (pinfunction "1_1") (pintype "input"))
      (node (ref "USBC1") (pin "A5") (pinfunction "CC1_A5") (pintype "unspecified"))
    )
    (net (code "41") (name "Net-(USBC1-CC2)") (class "Default")
      (node (ref "R10") (pin "2") (pinfunction "2_2") (pintype "input"))
      (node (ref "USBC1") (pin "B5") (pinfunction "CC2_B5") (pintype "unspecified"))
    )
    (net (code "42") (name "RXD0") (class "Default")
      (node (ref "U10") (pin "26") (pinfunction "TXD_26") (pintype "unspecified"))
      (node (ref "U2") (pin "34") (pinfunction "RXD0_34") (pintype "unspecified"))
    )
    (net (code "43") (name "SPEAKER_N") (class "Default")
      (node (ref "U1") (pin "10") (pinfunction "OUTN_10") (pintype "unspecified"))
    )
    (net (code "44") (name "SPEAKER_P") (class "Default")
      (node (ref "U1") (pin "9") (pinfunction "OUTP_9") (pintype "unspecified"))
    )
    (net (code "45") (name "TXD0") (class "Default")
      (node (ref "U10") (pin "25") (pinfunction "RXD_25") (pintype "unspecified"))
      (node (ref "U2") (pin "35") (pinfunction "TXD0_35") (pintype "unspecified"))
    )
    (net (code "46") (name "USB_D+") (class "Default")
      (node (ref "U10") (pin "4") (pinfunction "D+_4") (pintype "unspecified"))
      (node (ref "USBC1") (pin "A6") (pinfunction "DP1_A6") (pintype "unspecified"))
      (node (ref "USBC1") (pin "B6") (pinfunction "DP2_B6") (pintype "unspecified"))
    )
    (net (code "47") (name "USB_D-") (class "Default")
      (node (ref "U10") (pin "5") (pinfunction "D-_5") (pintype "unspecified"))
      (node (ref "USBC1") (pin "A7") (pinfunction "DN1_A7") (pintype "unspecified"))
      (node (ref "USBC1") (pin "B7") (pinfunction "DN2_B7") (pintype "unspecified"))
    )
    (net (code "48") (name "unconnected-(C14-Pad1)") (class "Default")
      (node (ref "C14") (pin "1") (pinfunction "1_1") (pintype "input"))
    )
    (net (code "49") (name "unconnected-(C14-Pad2)") (class "Default")
      (node (ref "C14") (pin "2") (pinfunction "2_2") (pintype "input"))
    )
    (net (code "50") (name "unconnected-(C15-Pad1)") (class "Default")
      (node (ref "C15") (pin "1") (pinfunction "1_1") (pintype "input"))
    )
    (net (code "51") (name "unconnected-(C15-Pad2)") (class "Default")
      (node (ref "C15") (pin "2") (pinfunction "2_2") (pintype "input"))
    )
    (net (code "52") (name "unconnected-(C18-Pad1)") (class "Default")
      (node (ref "C18") (pin "1") (pinfunction "1_1") (pintype "unspecified"))
    )
    (net (code "53") (name "unconnected-(C18-Pad2)") (class "Default")
      (node (ref "C18") (pin "2") (pinfunction "2_2") (pintype "unspecified"))
    )
    (net (code "54") (name "unconnected-(C19-Pad1)") (class "Default")
      (node (ref "C19") (pin "1") (pinfunction "1_1") (pintype "unspecified"))
    )
    (net (code "55") (name "unconnected-(C19-Pad2)") (class "Default")
      (node (ref "C19") (pin "2") (pinfunction "2_2") (pintype "unspecified"))
    )
    (net (code "56") (name "unconnected-(C20-Pad1)") (class "Default")
      (node (ref "C20") (pin "1") (pinfunction "1_1") (pintype "input"))
    )
    (net (code "57") (name "unconnected-(C20-Pad2)") (class "Default")
      (node (ref "C20") (pin "2") (pinfunction "2_2") (pintype "input"))
    )
    (net (code "58") (name "unconnected-(DC1-Pad3)") (class "Default")
      (node (ref "DC1") (pin "3") (pinfunction "3_3") (pintype "unspecified"))
    )
    (net (code "59") (name "unconnected-(DC2-Pad3)") (class "Default")
      (node (ref "DC2") (pin "3") (pinfunction "3_3") (pintype "unspecified"))
    )
    (net (code "60") (name "unconnected-(LED11-DOUT-Pad2)") (class "Default")
      (node (ref "LED11") (pin "2") (pinfunction "DOUT_2") (pintype "unspecified"))
    )
    (net (code "61") (name "unconnected-(U1-EP-Pad17)") (class "Default")
      (node (ref "U1") (pin "17") (pinfunction "EP_17") (pintype "unspecified"))
    )
    (net (code "62") (name "unconnected-(U1-N.C.-Pad5)") (class "Default")
      (node (ref "U1") (pin "5") (pinfunction "N.C._5") (pintype "unspecified"))
    )
    (net (code "63") (name "unconnected-(U1-N.C.-Pad6)") (class "Default")
      (node (ref "U1") (pin "6") (pinfunction "N.C._6") (pintype "unspecified"))
    )
    (net (code "64") (name "unconnected-(U1-N.C.-Pad12)") (class "Default")
      (node (ref "U1") (pin "12") (pinfunction "N.C._12") (pintype "unspecified"))
    )
    (net (code "65") (name "unconnected-(U1-N.C.-Pad13)") (class "Default")
      (node (ref "U1") (pin "13") (pinfunction "N.C._13") (pintype "unspecified"))
    )
    (net (code "66") (name "unconnected-(U1-SD_MODE#-Pad4)") (class "Default")
      (node (ref "U1") (pin "4") (pinfunction "SD_MODE#_4") (pintype "unspecified"))
    )
    (net (code "67") (name "unconnected-(U2-GND-Pad1)") (class "Default")
      (node (ref "U2") (pin "1") (pinfunction "GND_1") (pintype "unspecified"))
    )
    (net (code "68") (name "unconnected-(U2-GND-Pad15)") (class "Default")
      (node (ref "U2") (pin "15") (pinfunction "GND_15") (pintype "unspecified"))
    )
    (net (code "69") (name "unconnected-(U2-GND-Pad38)") (class "Default")
      (node (ref "U2") (pin "38") (pinfunction "GND_38") (pintype "unspecified"))
    )
    (net (code "70") (name "unconnected-(U2-GND-Pad39)") (class "Default")
      (node (ref "U2") (pin "39") (pinfunction "GND_39") (pintype "unspecified"))
    )
    (net (code "71") (name "unconnected-(U2-IO2-Pad24)") (class "Default")
      (node (ref "U2") (pin "24") (pinfunction "IO2_24") (pintype "unspecified"))
    )
    (net (code "72") (name "unconnected-(U2-IO4-Pad26)") (class "Default")
      (node (ref "U2") (pin "26") (pinfunction "IO4_26") (pintype "unspecified"))
    )
    (net (code "73") (name "unconnected-(U2-IO12-Pad14)") (class "Default")
      (node (ref "U2") (pin "14") (pinfunction "IO12_14") (pintype "unspecified"))
    )
    (net (code "74") (name "unconnected-(U2-IO13-Pad16)") (class "Default")
      (node (ref "U2") (pin "16") (pinfunction "IO13_16") (pintype "unspecified"))
    )
    (net (code "75") (name "unconnected-(U2-IO14-Pad13)") (class "Default")
      (node (ref "U2") (pin "13") (pinfunction "IO14_13") (pintype "unspecified"))
    )
    (net (code "76") (name "unconnected-(U2-IO15-Pad23)") (class "Default")
      (node (ref "U2") (pin "23") (pinfunction "IO15_23") (pintype "unspecified"))
    )
    (net (code "77") (name "unconnected-(U2-IO18-Pad30)") (class "Default")
      (node (ref "U2") (pin "30") (pinfunction "IO18_30") (pintype "unspecified"))
    )
    (net (code "78") (name "unconnected-(U2-IO19-Pad31)") (class "Default")
      (node (ref "U2") (pin "31") (pinfunction "IO19_31") (pintype "unspecified"))
    )
    (net (code "79") (name "unconnected-(U2-IO21-Pad33)") (class "Default")
      (node (ref "U2") (pin "33") (pinfunction "IO21_33") (pintype "unspecified"))
    )
    (net (code "80") (name "unconnected-(U2-IO23-Pad37)") (class "Default")
      (node (ref "U2") (pin "37") (pinfunction "IO23_37") (pintype "unspecified"))
    )
    (net (code "81") (name "unconnected-(U2-IO27-Pad12)") (class "Default")
      (node (ref "U2") (pin "12") (pinfunction "IO27_12") (pintype "unspecified"))
    )
    (net (code "82") (name "unconnected-(U2-IO32-Pad8)") (class "Default")
      (node (ref "U2") (pin "8") (pinfunction "IO32_8") (pintype "unspecified"))
    )
    (net (code "83") (name "unconnected-(U2-IO33-Pad9)") (class "Default")
      (node (ref "U2") (pin "9") (pinfunction "IO33_9") (pintype "unspecified"))
    )
    (net (code "84") (name "unconnected-(U2-IO34-Pad6)") (class "Default")
      (node (ref "U2") (pin "6") (pinfunction "IO34_6") (pintype "unspecified"))
    )
    (net (code "85") (name "unconnected-(U2-IO35-Pad7)") (class "Default")
      (node (ref "U2") (pin "7") (pinfunction "IO35_7") (pintype "unspecified"))
    )
    (net (code "86") (name "unconnected-(U2-NC-Pad17)") (class "Default")
      (node (ref "U2") (pin "17") (pinfunction "NC_17") (pintype "unspecified"))
    )
    (net (code "87") (name "unconnected-(U2-NC-Pad18)") (class "Default")
      (node (ref "U2") (pin "18") (pinfunction "NC_18") (pintype "unspecified"))
    )
    (net (code "88") (name "unconnected-(U2-NC-Pad19)") (class "Default")
      (node (ref "U2") (pin "19") (pinfunction "NC_19") (pintype "unspecified"))
    )
    (net (code "89") (name "unconnected-(U2-NC-Pad20)") (class "Default")
      (node (ref "U2") (pin "20") (pinfunction "NC_20") (pintype "unspecified"))
    )
    (net (code "90") (name "unconnected-(U2-NC-Pad21)") (class "Default")
      (node (ref "U2") (pin "21") (pinfunction "NC_21") (pintype "unspecified"))
    )
    (net (code "91") (name "unconnected-(U2-NC-Pad22)") (class "Default")
      (node (ref "U2") (pin "22") (pinfunction "NC_22") (pintype "unspecified"))
    )
    (net (code "92") (name "unconnected-(U2-NC-Pad27)") (class "Default")
      (node (ref "U2") (pin "27") (pinfunction "NC_27") (pintype "unspecified"))
    )
    (net (code "93") (name "unconnected-(U2-NC-Pad28)") (class "Default")
      (node (ref "U2") (pin "28") (pinfunction "NC_28") (pintype "unspecified"))
    )
    (net (code "94") (name "unconnected-(U2-NC-Pad32)") (class "Default")
      (node (ref "U2") (pin "32") (pinfunction "NC_32") (pintype "unspecified"))
    )
    (net (code "95") (name "unconnected-(U2-SENSOR_VN-Pad5)") (class "Default")
      (node (ref "U2") (pin "5") (pinfunction "SENSOR_VN_5") (pintype "unspecified"))
    )
    (net (code "96") (name "unconnected-(U2-SENSOR_VP-Pad4)") (class "Default")
      (node (ref "U2") (pin "4") (pinfunction "SENSOR_VP_4") (pintype "unspecified"))
    )
    (net (code "97") (name "unconnected-(U2-VDD33-Pad2)") (class "Default")
      (node (ref "U2") (pin "2") (pinfunction "VDD33_2") (pintype "unspecified"))
    )
    (net (code "98") (name "unconnected-(U4-ADR{slash}FAULT#-Pad3)") (class "Default")
      (node (ref "U4") (pin "3") (pinfunction "ADR/FAULT#_3") (pintype "unspecified"))
    )
    (net (code "99") (name "unconnected-(U4-AGND-Pad14)") (class "Default")
      (node (ref "U4") (pin "14") (pinfunction "AGND_14") (pintype "unspecified"))
    )
    (net (code "100") (name "unconnected-(U4-AVDD-Pad13)") (class "Default")
      (node (ref "U4") (pin "13") (pinfunction "AVDD_13") (pintype "unspecified"))
    )
    (net (code "101") (name "unconnected-(U4-BST_A+-Pad25)") (class "Default")
      (node (ref "U4") (pin "25") (pinfunction "BST_A+_25") (pintype "unspecified"))
    )
    (net (code "102") (name "unconnected-(U4-BST_A--Pad22)") (class "Default")
      (node (ref "U4") (pin "22") (pinfunction "BST_A-_22") (pintype "unspecified"))
    )
    (net (code "103") (name "unconnected-(U4-BST_B+-Pad18)") (class "Default")
      (node (ref "U4") (pin "18") (pinfunction "BST_B+_18") (pintype "unspecified"))
    )
    (net (code "104") (name "unconnected-(U4-BST_B--Pad21)") (class "Default")
      (node (ref "U4") (pin "21") (pinfunction "BST_B-_21") (pintype "unspecified"))
    )
    (net (code "105") (name "unconnected-(U4-DGND-Pad1)") (class "Default")
      (node (ref "U4") (pin "1") (pinfunction "DGND_1") (pintype "unspecified"))
    )
    (net (code "106") (name "unconnected-(U4-DGND-Pad5)") (class "Default")
      (node (ref "U4") (pin "5") (pinfunction "DGND_5") (pintype "unspecified"))
    )
    (net (code "107") (name "unconnected-(U4-DVDD-Pad2)") (class "Default")
      (node (ref "U4") (pin "2") (pinfunction "DVDD_2") (pintype "unspecified"))
    )
    (net (code "108") (name "unconnected-(U4-EP-Pad29)") (class "Default")
      (node (ref "U4") (pin "29") (pinfunction "EP_29") (pintype "unspecified"))
    )
    (net (code "109") (name "unconnected-(U4-LRCLK-Pad6)") (class "Default")
      (node (ref "U4") (pin "6") (pinfunction "LRCLK_6") (pintype "unspecified"))
    )
    (net (code "110") (name "unconnected-(U4-OUT_A+-Pad26)") (class "Default")
      (node (ref "U4") (pin "26") (pinfunction "OUT_A+_26") (pintype "unspecified"))
    )
    (net (code "111") (name "unconnected-(U4-OUT_A--Pad23)") (class "Default")
      (node (ref "U4") (pin "23") (pinfunction "OUT_A-_23") (pintype "unspecified"))
    )
    (net (code "112") (name "unconnected-(U4-OUT_B+-Pad17)") (class "Default")
      (node (ref "U4") (pin "17") (pinfunction "OUT_B+_17") (pintype "unspecified"))
    )
    (net (code "113") (name "unconnected-(U4-OUT_B--Pad20)") (class "Default")
      (node (ref "U4") (pin "20") (pinfunction "OUT_B-_20") (pintype "unspecified"))
    )
    (net (code "114") (name "unconnected-(U4-PDN#-Pad12)") (class "Default")
      (node (ref "U4") (pin "12") (pinfunction "PDN#_12") (pintype "unspecified"))
    )
    (net (code "115") (name "unconnected-(U4-PGND-Pad19)") (class "Default")
      (node (ref "U4") (pin "19") (pinfunction "PGND_19") (pintype "unspecified"))
    )
    (net (code "116") (name "unconnected-(U4-PGND-Pad24)") (class "Default")
      (node (ref "U4") (pin "24") (pinfunction "PGND_24") (pintype "unspecified"))
    )
    (net (code "117") (name "unconnected-(U4-PVDD-Pad15)") (class "Default")
      (node (ref "U4") (pin "15") (pinfunction "PVDD_15") (pintype "unspecified"))
    )
    (net (code "118") (name "unconnected-(U4-PVDD-Pad16)") (class "Default")
      (node (ref "U4") (pin "16") (pinfunction "PVDD_16") (pintype "unspecified"))
    )
    (net (code "119") (name "unconnected-(U4-PVDD-Pad27)") (class "Default")
      (node (ref "U4") (pin "27") (pinfunction "PVDD_27") (pintype "unspecified"))
    )
    (net (code "120") (name "unconnected-(U4-PVDD-Pad28)") (class "Default")
      (node (ref "U4") (pin "28") (pinfunction "PVDD_28") (pintype "unspecified"))
    )
    (net (code "121") (name "unconnected-(U4-SCL-Pad11)") (class "Default")
      (node (ref "U4") (pin "11") (pinfunction "SCL_11") (pintype "unspecified"))
    )
    (net (code "122") (name "unconnected-(U4-SCLK-Pad7)") (class "Default")
      (node (ref "U4") (pin "7") (pinfunction "SCLK_7") (pintype "unspecified"))
    )
    (net (code "123") (name "unconnected-(U4-SDA-Pad10)") (class "Default")
      (node (ref "U4") (pin "10") (pinfunction "SDA_10") (pintype "unspecified"))
    )
    (net (code "124") (name "unconnected-(U4-SDIN-Pad8)") (class "Default")
      (node (ref "U4") (pin "8") (pinfunction "SDIN_8") (pintype "unspecified"))
    )
    (net (code "125") (name "unconnected-(U4-SDOUT-Pad9)") (class "Default")
      (node (ref "U4") (pin "9") (pinfunction "SDOUT_9") (pintype "unspecified"))
    )
    (net (code "126") (name "unconnected-(U4-VR_DIG-Pad4)") (class "Default")
      (node (ref "U4") (pin "4") (pinfunction "VR_DIG_4") (pintype "unspecified"))
    )
    (net (code "127") (name "unconnected-(U7-FB-Pad4)") (class "Default")
      (node (ref "U7") (pin "4") (pinfunction "FB_4") (pintype "unspecified"))
    )
    (net (code "128") (name "unconnected-(U7-GND-Pad3)") (class "Default")
      (node (ref "U7") (pin "3") (pinfunction "GND_3") (pintype "unspecified"))
    )
    (net (code "129") (name "unconnected-(U7-ON{slash}OFF-Pad5)") (class "Default")
      (node (ref "U7") (pin "5") (pinfunction "ON/OFF_5") (pintype "unspecified"))
    )
    (net (code "130") (name "unconnected-(U7-OUT-Pad2)") (class "Default")
      (node (ref "U7") (pin "2") (pinfunction "OUT_2") (pintype "unspecified"))
    )
    (net (code "131") (name "unconnected-(U7-TAB-Pad6)") (class "Default")
      (node (ref "U7") (pin "6") (pinfunction "TAB_6") (pintype "unspecified"))
    )
    (net (code "132") (name "unconnected-(U7-VIN-Pad1)") (class "Default")
      (node (ref "U7") (pin "1") (pinfunction "VIN_1") (pintype "unspecified"))
    )
    (net (code "133") (name "unconnected-(U8-EN-Pad3)") (class "Default")
      (node (ref "U8") (pin "3") (pinfunction "EN_3") (pintype "unspecified"))
    )
    (net (code "134") (name "unconnected-(U8-GND-Pad4)") (class "Default")
      (node (ref "U8") (pin "4") (pinfunction "GND_4") (pintype "unspecified"))
    )
    (net (code "135") (name "unconnected-(U8-ITH-Pad2)") (class "Default")
      (node (ref "U8") (pin "2") (pinfunction "ITH_2") (pintype "unspecified"))
    )
    (net (code "136") (name "unconnected-(U8-PGND-Pad5)") (class "Default")
      (node (ref "U8") (pin "5") (pinfunction "PGND_5") (pintype "unspecified"))
    )
    (net (code "137") (name "unconnected-(U8-PVCC-Pad7)") (class "Default")
      (node (ref "U8") (pin "7") (pinfunction "PVCC_7") (pintype "unspecified"))
    )
    (net (code "138") (name "unconnected-(U8-SW-Pad6)") (class "Default")
      (node (ref "U8") (pin "6") (pinfunction "SW_6") (pintype "unspecified"))
    )
    (net (code "139") (name "unconnected-(U8-VCC-Pad8)") (class "Default")
      (node (ref "U8") (pin "8") (pinfunction "VCC_8") (pintype "unspecified"))
    )
    (net (code "140") (name "unconnected-(U8-VOUT-Pad1)") (class "Default")
      (node (ref "U8") (pin "1") (pinfunction "VOUT_1") (pintype "unspecified"))
    )
    (net (code "141") (name "unconnected-(U10-CTS-Pad23)") (class "Default")
      (node (ref "U10") (pin "23") (pinfunction "CTS_23") (pintype "unspecified"))
    )
    (net (code "142") (name "unconnected-(U10-DCD-Pad1)") (class "Default")
      (node (ref "U10") (pin "1") (pinfunction "DCD_1") (pintype "unspecified"))
    )
    (net (code "143") (name "unconnected-(U10-DSR-Pad27)") (class "Default")
      (node (ref "U10") (pin "27") (pinfunction "DSR_27") (pintype "unspecified"))
    )
    (net (code "144") (name "unconnected-(U10-DTR-Pad28)") (class "Default")
      (node (ref "U10") (pin "28") (pinfunction "DTR_28") (pintype "unspecified"))
    )
    (net (code "145") (name "unconnected-(U10-EP-Pad29)") (class "Default")
      (node (ref "U10") (pin "29") (pinfunction "EP_29") (pintype "unspecified"))
    )
    (net (code "146") (name "unconnected-(U10-GND-Pad3)") (class "Default")
      (node (ref "U10") (pin "3") (pinfunction "GND_3") (pintype "unspecified"))
    )
    (net (code "147") (name "unconnected-(U10-NC-Pad10)") (class "Default")
      (node (ref "U10") (pin "10") (pinfunction "NC_10") (pintype "unspecified"))
    )
    (net (code "148") (name "unconnected-(U10-NC-Pad13)") (class "Default")
      (node (ref "U10") (pin "13") (pinfunction "NC_13") (pintype "unspecified"))
    )
    (net (code "149") (name "unconnected-(U10-NC-Pad14)") (class "Default")
      (node (ref "U10") (pin "14") (pinfunction "NC_14") (pintype "unspecified"))
    )
    (net (code "150") (name "unconnected-(U10-NC-Pad15)") (class "Default")
      (node (ref "U10") (pin "15") (pinfunction "NC_15") (pintype "unspecified"))
    )
    (net (code "151") (name "unconnected-(U10-NC-Pad16)") (class "Default")
      (node (ref "U10") (pin "16") (pinfunction "NC_16") (pintype "unspecified"))
    )
    (net (code "152") (name "unconnected-(U10-NC-Pad17)") (class "Default")
      (node (ref "U10") (pin "17") (pinfunction "NC_17") (pintype "unspecified"))
    )
    (net (code "153") (name "unconnected-(U10-NC-Pad18)") (class "Default")
      (node (ref "U10") (pin "18") (pinfunction "NC_18") (pintype "unspecified"))
    )
    (net (code "154") (name "unconnected-(U10-NC-Pad19)") (class "Default")
      (node (ref "U10") (pin "19") (pinfunction "NC_19") (pintype "unspecified"))
    )
    (net (code "155") (name "unconnected-(U10-NC-Pad20)") (class "Default")
      (node (ref "U10") (pin "20") (pinfunction "NC_20") (pintype "unspecified"))
    )
    (net (code "156") (name "unconnected-(U10-NC-Pad21)") (class "Default")
      (node (ref "U10") (pin "21") (pinfunction "NC_21") (pintype "unspecified"))
    )
    (net (code "157") (name "unconnected-(U10-NC-Pad22)") (class "Default")
      (node (ref "U10") (pin "22") (pinfunction "NC_22") (pintype "unspecified"))
    )
    (net (code "158") (name "unconnected-(U10-REGIN-Pad7)") (class "Default")
      (node (ref "U10") (pin "7") (pinfunction "REGIN_7") (pintype "unspecified"))
    )
    (net (code "159") (name "unconnected-(U10-RI-Pad2)") (class "Default")
      (node (ref "U10") (pin "2") (pinfunction "RI_2") (pintype "unspecified"))
    )
    (net (code "160") (name "unconnected-(U10-RST#-Pad9)") (class "Default")
      (node (ref "U10") (pin "9") (pinfunction "RST#_9") (pintype "unspecified"))
    )
    (net (code "161") (name "unconnected-(U10-RTS-Pad24)") (class "Default")
      (node (ref "U10") (pin "24") (pinfunction "RTS_24") (pintype "unspecified"))
    )
    (net (code "162") (name "unconnected-(U10-SUSPEND#-Pad11)") (class "Default")
      (node (ref "U10") (pin "11") (pinfunction "SUSPEND#_11") (pintype "unspecified"))
    )
    (net (code "163") (name "unconnected-(U10-SUSPEND-Pad12)") (class "Default")
      (node (ref "U10") (pin "12") (pinfunction "SUSPEND_12") (pintype "unspecified"))
    )
    (net (code "164") (name "unconnected-(U10-VDD-Pad6)") (class "Default")
      (node (ref "U10") (pin "6") (pinfunction "VDD_6") (pintype "unspecified"))
    )
    (net (code "165") (name "unconnected-(USBC1-SBU1-PadA8)") (class "Default")
      (node (ref "USBC1") (pin "A8") (pinfunction "SBU1_A8") (pintype "unspecified"))
    )
    (net (code "166") (name "unconnected-(USBC1-SBU2-PadB8)") (class "Default")
      (node (ref "USBC1") (pin "B8") (pinfunction "SBU2_B8") (pintype "unspecified"))
    )
  )
)
